# prg-flash.net
KiCad netlist of a schematic drawn in Altium Designer
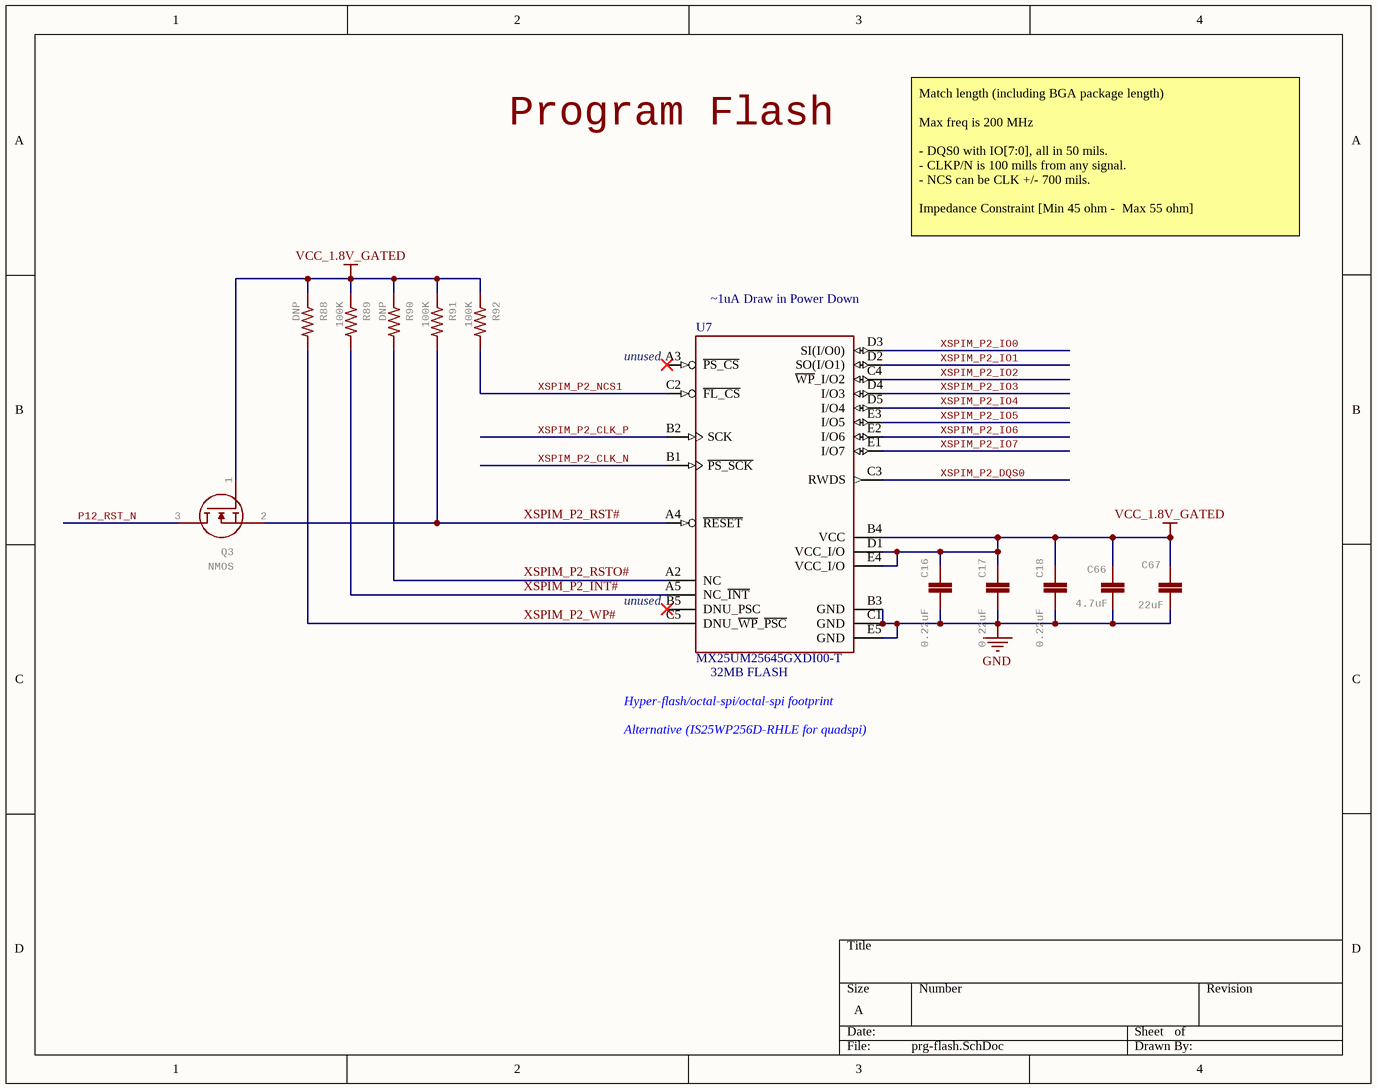
[diagram p0: prg-flash.SchDoc]

(export (version "E")
  (design (tool "Eeschema 10.0.6"))
  (components
    (comp (ref "C16")
      (value "0.22uF")
      (footprint "C0201")
      (description "CAPACITOR, European symbol")
      (fields (field (name "MPN") "GRM033R60J224ME15D"))
      (libsource (lib "rt10") (part "C-EUC0201"))
    )
    (comp (ref "C17")
      (value "0.22uF")
      (footprint "C0201")
      (description "CAPACITOR, European symbol")
      (fields (field (name "MPN") "GRM033R60J224ME15D"))
      (libsource (lib "rt10") (part "C-EUC0201"))
    )
    (comp (ref "C18")
      (value "0.22uF")
      (footprint "C0201")
      (description "CAPACITOR, European symbol")
      (fields (field (name "MPN") "GRM033R60J224ME15D"))
      (libsource (lib "rt10") (part "C-EUC0201"))
    )
    (comp (ref "C66")
      (value "4.7uF")
      (footprint "0402-CAP")
      (description "CapacitorStandard 0603 ceramic capacitor, and 0.1\" leaded capacitor.")
      (fields (field (name "MPN") "JMK105BBJ475MV-F"))
      (libsource (lib "openmv-ae3") (part "CAP0402-CAP"))
    )
    (comp (ref "C67")
      (value "22uF")
      (footprint "0805")
      (fields (field (name "MPN") "CL21A226MQQNNNE"))
      (libsource (lib "openmv-ae3") (part "22UF-0805-6.3V-20%"))
    )
    (comp (ref "Q3") (value "NMOS") (footprint "DFN1006") (libsource (lib "rt10") (part "2N7002KW_R1_00001")))
    (comp (ref "R88")
      (value "DNP")
      (footprint "0402-RES")
      (description "ResistorBasic schematic elements and footprints for 0603, 1206, and PTH resistors.")
      (libsource (lib "openmv-ae3") (part "RESISTOR0402-RES"))
    )
    (comp (ref "R89")
      (value "100K")
      (footprint "0402-RES")
      (description "ResistorBasic schematic elements and footprints for 0603, 1206, and PTH resistors.")
      (fields (field (name "MPN") "AC0402FR-07100KL"))
      (libsource (lib "openmv-ae3") (part "RESISTOR0402-RES"))
    )
    (comp (ref "R90")
      (value "DNP")
      (footprint "0402-RES")
      (description "ResistorBasic schematic elements and footprints for 0603, 1206, and PTH resistors.")
      (libsource (lib "openmv-ae3") (part "RESISTOR0402-RES"))
    )
    (comp (ref "R91")
      (value "100K")
      (footprint "0402-RES")
      (description "ResistorBasic schematic elements and footprints for 0603, 1206, and PTH resistors.")
      (fields (field (name "MPN") "AC0402FR-07100KL"))
      (libsource (lib "openmv-ae3") (part "RESISTOR0402-RES"))
    )
    (comp (ref "R92")
      (value "100K")
      (footprint "0402-RES")
      (description "ResistorBasic schematic elements and footprints for 0603, 1206, and PTH resistors.")
      (fields (field (name "MPN") "AC0402FR-07100KL"))
      (libsource (lib "openmv-ae3") (part "RESISTOR0402-RES"))
    )
    (comp (ref "U7")
      (value "MX25UM25645GXDI00-T")
      (footprint "24-TBGA")
      (description "IC, Flash,32MB x 8, Octal SPI, Ind Temp, 1.8V,24-BGA")
      (fields (field (name "MPN") "MX25UM25645GXDI00-T"))
      (libsource (lib "openmv-ae3") (part "IS25WX256-JHLE"))
    )
  )
  (nets
    (net (code "1") (name "/P12_RST_N") (class "Default")
      (node (ref "Q3") (pin "3") (pinfunction "D_3") (pintype "bidirectional"))
    )
    (net (code "2") (name "/XSPIM_P2_CLK_N") (class "Default")
      (node (ref "U7") (pin "B1") (pinfunction "~{PS_SCK}_B1") (pintype "input"))
    )
    (net (code "3") (name "/XSPIM_P2_CLK_P") (class "Default")
      (node (ref "U7") (pin "B2") (pinfunction "SCK_B2") (pintype "input"))
    )
    (net (code "4") (name "/XSPIM_P2_DQS0") (class "Default")
      (node (ref "U7") (pin "C3") (pinfunction "RWDS_C3") (pintype "output"))
    )
    (net (code "5") (name "/XSPIM_P2_INT#") (class "Default")
      (node (ref "R89") (pin "2") (pinfunction "2_2") (pintype "passive"))
      (node (ref "U7") (pin "A5") (pinfunction "NC_~{INT}_A5") (pintype "passive"))
    )
    (net (code "6") (name "/XSPIM_P2_IO0") (class "Default")
      (node (ref "U7") (pin "D3") (pinfunction "SI(I/O0)_D3") (pintype "bidirectional"))
    )
    (net (code "7") (name "/XSPIM_P2_IO1") (class "Default")
      (node (ref "U7") (pin "D2") (pinfunction "SO(I/O1)_D2") (pintype "bidirectional"))
    )
    (net (code "8") (name "/XSPIM_P2_IO2") (class "Default")
      (node (ref "U7") (pin "C4") (pinfunction "~{WP}_I/O2_C4") (pintype "bidirectional"))
    )
    (net (code "9") (name "/XSPIM_P2_IO3") (class "Default")
      (node (ref "U7") (pin "D4") (pinfunction "I/O3_D4") (pintype "bidirectional"))
    )
    (net (code "10") (name "/XSPIM_P2_IO4") (class "Default")
      (node (ref "U7") (pin "D5") (pinfunction "I/O4_D5") (pintype "bidirectional"))
    )
    (net (code "11") (name "/XSPIM_P2_IO5") (class "Default")
      (node (ref "U7") (pin "E3") (pinfunction "I/O5_E3") (pintype "bidirectional"))
    )
    (net (code "12") (name "/XSPIM_P2_IO6") (class "Default")
      (node (ref "U7") (pin "E2") (pinfunction "I/O6_E2") (pintype "bidirectional"))
    )
    (net (code "13") (name "/XSPIM_P2_IO7") (class "Default")
      (node (ref "U7") (pin "E1") (pinfunction "I/O7_E1") (pintype "bidirectional"))
    )
    (net (code "14") (name "/XSPIM_P2_NCS1") (class "Default")
      (node (ref "R92") (pin "2") (pinfunction "2_2") (pintype "passive"))
      (node (ref "U7") (pin "C2") (pinfunction "~{FL_CS}_C2") (pintype "input"))
    )
    (net (code "15") (name "/XSPIM_P2_RST#") (class "Default")
      (node (ref "Q3") (pin "2") (pinfunction "S_2") (pintype "bidirectional"))
      (node (ref "R91") (pin "2") (pinfunction "2_2") (pintype "passive"))
      (node (ref "U7") (pin "A4") (pinfunction "~{RESET}_A4") (pintype "input"))
    )
    (net (code "16") (name "/XSPIM_P2_RSTO#") (class "Default")
      (node (ref "R90") (pin "2") (pinfunction "2_2") (pintype "passive"))
      (node (ref "U7") (pin "A2") (pinfunction "NC_A2") (pintype "passive"))
    )
    (net (code "17") (name "/XSPIM_P2_WP#") (class "Default")
      (node (ref "R88") (pin "2") (pinfunction "2_2") (pintype "passive"))
      (node (ref "U7") (pin "C5") (pinfunction "DNU_~{WP}_~{PSC}_C5") (pintype "passive"))
    )
    (net (code "18") (name "GND") (class "Default")
      (node (ref "C16") (pin "2") (pinfunction "2_2") (pintype "passive"))
      (node (ref "C17") (pin "2") (pinfunction "2_2") (pintype "passive"))
      (node (ref "C18") (pin "2") (pinfunction "2_2") (pintype "passive"))
      (node (ref "C66") (pin "1") (pinfunction "1_1") (pintype "passive"))
      (node (ref "C67") (pin "1") (pinfunction "1_1") (pintype "passive"))
      (node (ref "U7") (pin "B3") (pinfunction "GND_B3") (pintype "power_in"))
      (node (ref "U7") (pin "C1") (pinfunction "GND_C1") (pintype "power_in"))
      (node (ref "U7") (pin "E5") (pinfunction "GND_E5") (pintype "power_in"))
    )
    (net (code "19") (name "VCC_1.8V_GATED") (class "Default")
      (node (ref "C16") (pin "1") (pinfunction "1_1") (pintype "passive"))
      (node (ref "C17") (pin "1") (pinfunction "1_1") (pintype "passive"))
      (node (ref "C18") (pin "1") (pinfunction "1_1") (pintype "passive"))
      (node (ref "C66") (pin "2") (pinfunction "2_2") (pintype "passive"))
      (node (ref "C67") (pin "2") (pinfunction "2_2") (pintype "passive"))
      (node (ref "Q3") (pin "1") (pinfunction "G_1") (pintype "bidirectional"))
      (node (ref "R88") (pin "1") (pinfunction "1_1") (pintype "passive"))
      (node (ref "R89") (pin "1") (pinfunction "1_1") (pintype "passive"))
      (node (ref "R90") (pin "1") (pinfunction "1_1") (pintype "passive"))
      (node (ref "R91") (pin "1") (pinfunction "1_1") (pintype "passive"))
      (node (ref "R92") (pin "1") (pinfunction "1_1") (pintype "passive"))
      (node (ref "U7") (pin "B4") (pinfunction "VCC_B4") (pintype "power_in"))
      (node (ref "U7") (pin "D1") (pinfunction "VCC_I/O_D1") (pintype "power_in"))
      (node (ref "U7") (pin "E4") (pinfunction "VCC_I/O_E4") (pintype "power_in"))
    )
    (net (code "20") (name "unconnected-(U7-DNU_PSC-PadB5)") (class "Default")
      (node (ref "U7") (pin "B5") (pinfunction "DNU_PSC_B5") (pintype "passive+no_connect"))
    )
    (net (code "21") (name "unconnected-(U7-~{PS_CS}-PadA3)") (class "Default")
      (node (ref "U7") (pin "A3") (pinfunction "~{PS_CS}_A3") (pintype "input+no_connect"))
    )
  )
)
